# Sheet2.net
KiCad netlist of a schematic drawn in Altium Designer
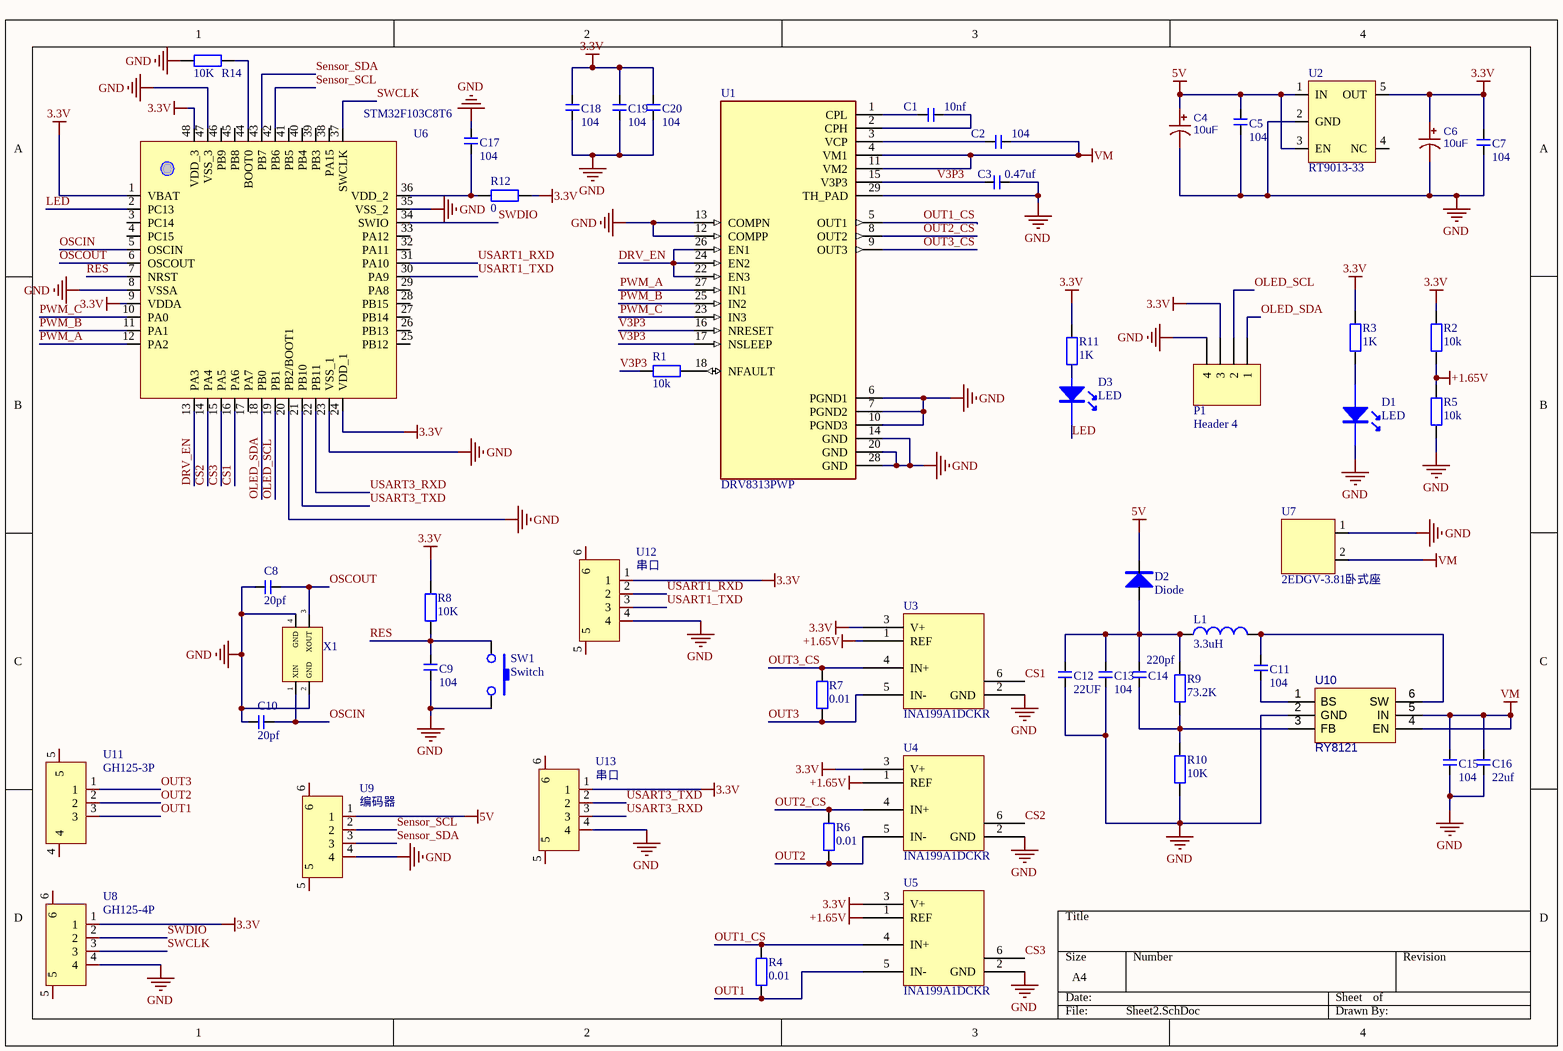
[diagram p0: Sheet2.SchDoc]

(export (version "E")
  (design (tool "Eeschema 10.0.6"))
  (components
    (comp (ref "C1")
      (value "10nf")
      (footprint "鹏鹏总结的pcb库:C0603")
      (description "无极性电容")
      (fields (field (name "版权归属") "源创客"))
      (libsource (lib "鹏鹏总结的原理库") (part "C"))
    )
    (comp (ref "C2")
      (value "104")
      (footprint "鹏鹏总结的pcb库:C0603")
      (description "无极性电容")
      (fields (field (name "版权归属") "源创客"))
      (libsource (lib "鹏鹏总结的原理库") (part "C"))
    )
    (comp (ref "C3")
      (value "0.47uf")
      (footprint "鹏鹏总结的pcb库:C0603")
      (description "无极性电容")
      (fields (field (name "版权归属") "源创客"))
      (libsource (lib "鹏鹏总结的原理库") (part "C"))
    )
    (comp (ref "C4")
      (value "10uF")
      (footprint "CD A(3216)")
      (description "电解电容 10uf  贴片型 钽电容的正极是实物有线的一段")
      (fields
        (field (name "BOM_MANUFACTURER PART") "RVT1V100M0405")
        (field (name "BOM_SUPPLIER PART") "C72485")
      )
      (libsource (lib "鹏鹏总结的原理库") (part "CAP+"))
    )
    (comp (ref "C5")
      (value "104")
      (footprint "鹏鹏总结的pcb库:C0603")
      (description "无极性电容")
      (fields (field (name "版权归属") "源创客"))
      (libsource (lib "鹏鹏总结的原理库") (part "C"))
    )
    (comp (ref "C6")
      (value "10uF")
      (footprint "CD A(3216)")
      (description "电解电容 10uf  贴片型 钽电容的正极是实物有线的一段")
      (fields
        (field (name "BOM_MANUFACTURER PART") "RVT1V100M0405")
        (field (name "BOM_SUPPLIER PART") "C72485")
      )
      (libsource (lib "鹏鹏总结的原理库") (part "CAP+"))
    )
    (comp (ref "C7")
      (value "104")
      (footprint "鹏鹏总结的pcb库:C0603")
      (description "无极性电容")
      (fields (field (name "版权归属") "源创客"))
      (libsource (lib "鹏鹏总结的原理库") (part "C"))
    )
    (comp (ref "C8")
      (value "20pf")
      (footprint "鹏鹏总结的pcb库:C0603")
      (description "无极性电容")
      (fields (field (name "版权归属") "源创客"))
      (libsource (lib "鹏鹏总结的原理库") (part "C"))
    )
    (comp (ref "C9")
      (value "104")
      (footprint "鹏鹏总结的pcb库:C0603")
      (description "无极性电容")
      (fields (field (name "版权归属") "源创客"))
      (libsource (lib "鹏鹏总结的原理库") (part "C"))
    )
    (comp (ref "C10")
      (value "20pf")
      (footprint "鹏鹏总结的pcb库:C0603")
      (description "无极性电容")
      (fields (field (name "版权归属") "源创客"))
      (libsource (lib "鹏鹏总结的原理库") (part "C"))
    )
    (comp (ref "C11")
      (value "104")
      (footprint "鹏鹏总结的pcb库:C0402")
      (description "无极性电容")
      (fields (field (name "版权归属") "源创客"))
      (libsource (lib "鹏鹏总结的原理库") (part "C"))
    )
    (comp (ref "C12")
      (value "22UF")
      (footprint "鹏鹏总结的pcb库:C0402")
      (description "无极性电容")
      (fields (field (name "版权归属") "源创客"))
      (libsource (lib "鹏鹏总结的原理库") (part "C"))
    )
    (comp (ref "C13")
      (value "104")
      (footprint "鹏鹏总结的pcb库:C0402")
      (description "无极性电容")
      (fields (field (name "版权归属") "源创客"))
      (libsource (lib "鹏鹏总结的原理库") (part "C"))
    )
    (comp (ref "C14")
      (value "220pf")
      (footprint "鹏鹏总结的pcb库:C0402")
      (description "无极性电容")
      (fields (field (name "版权归属") "源创客"))
      (libsource (lib "鹏鹏总结的原理库") (part "C"))
    )
    (comp (ref "C15")
      (value "104")
      (footprint "鹏鹏总结的pcb库:C0402")
      (description "无极性电容")
      (fields (field (name "版权归属") "源创客"))
      (libsource (lib "鹏鹏总结的原理库") (part "C"))
    )
    (comp (ref "C16")
      (value "22uf")
      (footprint "鹏鹏总结的pcb库:C0402")
      (description "无极性电容")
      (fields (field (name "版权归属") "源创客"))
      (libsource (lib "鹏鹏总结的原理库") (part "C"))
    )
    (comp (ref "C17")
      (value "104")
      (footprint "鹏鹏总结的pcb库:C0603")
      (description "无极性电容")
      (fields (field (name "版权归属") "源创客"))
      (libsource (lib "鹏鹏总结的原理库") (part "C"))
    )
    (comp (ref "C18")
      (value "104")
      (footprint "鹏鹏总结的pcb库:C0603")
      (description "无极性电容")
      (fields (field (name "版权归属") "源创客"))
      (libsource (lib "鹏鹏总结的原理库") (part "C"))
    )
    (comp (ref "C19")
      (value "104")
      (footprint "鹏鹏总结的pcb库:C0603")
      (description "无极性电容")
      (fields (field (name "版权归属") "源创客"))
      (libsource (lib "鹏鹏总结的原理库") (part "C"))
    )
    (comp (ref "C20")
      (value "104")
      (footprint "鹏鹏总结的pcb库:C0603")
      (description "无极性电容")
      (fields (field (name "版权归属") "源创客"))
      (libsource (lib "鹏鹏总结的原理库") (part "C"))
    )
    (comp (ref "D1") (value "LED") (footprint "LED0402") (libsource (lib "鹏鹏总结的原理库") (part "LED")))
    (comp (ref "D2")
      (value "Diode")
      (footprint "ESC_L1.2-W0.8-LS1.6-RD")
      (description "Diode 1N series")
      (libsource (lib "鹏鹏总结的原理库") (part "二极管"))
    )
    (comp (ref "D3") (value "LED") (footprint "LED0402") (libsource (lib "鹏鹏总结的原理库") (part "LED")))
    (comp (ref "L1")
      (value "3.3uH")
      (footprint "0402 TPC 4*4*2")
      (description "电感")
      (fields (field (name "版权归属") "源创客"))
      (libsource (lib "鹏鹏总结的原理库") (part "L"))
    )
    (comp (ref "P1")
      (value "Header 4")
      (footprint "HDR1X4")
      (description "Header, 4-Pin")
      (fields (field (name "PUBLISHER") "Altium Limited"))
      (libsource (lib "Miscellaneous Connectors") (part "Header 4"))
    )
    (comp (ref "R1")
      (value "10k")
      (footprint "鹏鹏总结的pcb库:R0603")
      (description "电阻")
      (fields (field (name "版权归属") "源创客"))
      (libsource (lib "鹏鹏总结的原理库") (part "R"))
    )
    (comp (ref "R2")
      (value "10k")
      (footprint "鹏鹏总结的pcb库:R0603")
      (description "电阻")
      (fields (field (name "版权归属") "源创客"))
      (libsource (lib "鹏鹏总结的原理库") (part "R"))
    )
    (comp (ref "R3")
      (value "1K")
      (footprint "R0402")
      (description "电阻")
      (fields (field (name "版权归属") "源创客"))
      (libsource (lib "鹏鹏总结的原理库") (part "R"))
    )
    (comp (ref "R4")
      (value "0.01")
      (footprint "R1206")
      (description "电阻")
      (fields (field (name "版权归属") "源创客"))
      (libsource (lib "鹏鹏总结的原理库") (part "R"))
    )
    (comp (ref "R5")
      (value "10k")
      (footprint "鹏鹏总结的pcb库:R0603")
      (description "电阻")
      (fields (field (name "版权归属") "源创客"))
      (libsource (lib "鹏鹏总结的原理库") (part "R"))
    )
    (comp (ref "R6")
      (value "0.01")
      (footprint "R1206")
      (description "电阻")
      (fields (field (name "版权归属") "源创客"))
      (libsource (lib "鹏鹏总结的原理库") (part "R"))
    )
    (comp (ref "R7")
      (value "0.01")
      (footprint "R1206")
      (description "电阻")
      (fields (field (name "版权归属") "源创客"))
      (libsource (lib "鹏鹏总结的原理库") (part "R"))
    )
    (comp (ref "R8")
      (value "10K")
      (footprint "鹏鹏总结的pcb库:R0603")
      (description "电阻")
      (fields (field (name "版权归属") "源创客"))
      (libsource (lib "鹏鹏总结的原理库") (part "R"))
    )
    (comp (ref "R9")
      (value "73.2K")
      (footprint "鹏鹏总结的pcb库:R0603")
      (description "电阻")
      (fields (field (name "版权归属") "源创客"))
      (libsource (lib "鹏鹏总结的原理库") (part "R"))
    )
    (comp (ref "R10")
      (value "10K")
      (footprint "鹏鹏总结的pcb库:R0603")
      (description "电阻")
      (fields (field (name "版权归属") "源创客"))
      (libsource (lib "鹏鹏总结的原理库") (part "R"))
    )
    (comp (ref "R11")
      (value "1K")
      (footprint "R0402")
      (description "电阻")
      (fields (field (name "版权归属") "源创客"))
      (libsource (lib "鹏鹏总结的原理库") (part "R"))
    )
    (comp (ref "R12")
      (value "0")
      (footprint "鹏鹏总结的pcb库:R0603")
      (description "电阻")
      (fields (field (name "版权归属") "源创客"))
      (libsource (lib "鹏鹏总结的原理库") (part "R"))
    )
    (comp (ref "R14")
      (value "10K")
      (footprint "鹏鹏总结的pcb库:R0603")
      (description "电阻")
      (fields (field (name "版权归属") "源创客"))
      (libsource (lib "鹏鹏总结的原理库") (part "R"))
    )
    (comp (ref "SW1")
      (value "Switch")
      (footprint "SW-SMD_L3.9-W3.6-LS4.8-EH")
      (description "SWITCH")
      (libsource (lib "鹏鹏总结的原理库") (part "Switch"))
    )
    (comp (ref "U1")
      (value "DRV8313PWP")
      (footprint "HTSSOP-28")
      (description "65-V max, 3-A peak 3-phase motor driver 28-HTSSOP -40 to 125")
      (fields (field (name "MF") "Texas Instruments"))
      (libsource (lib "鹏鹏总结的原理库") (part "DRV8313PWP"))
    )
    (comp (ref "U2")
      (value "RT9013-33")
      (footprint "SOT-23-5_L2.9-W1.6-P0.95-LS2.8-BR")
      (description "3.3V降压 500mA 最大输入5.5V")
      (libsource (lib "鹏鹏总结的原理库") (part "RT9013-33"))
    )
    (comp (ref "U3")
      (value "INA199A1DCKR")
      (footprint "SOT363")
      (libsource (lib "鹏鹏总结的原理库") (part "INA199A1DCKR"))
    )
    (comp (ref "U4")
      (value "INA199A1DCKR")
      (footprint "SOT363")
      (libsource (lib "鹏鹏总结的原理库") (part "INA199A1DCKR"))
    )
    (comp (ref "U5")
      (value "INA199A1DCKR")
      (footprint "SOT363")
      (libsource (lib "鹏鹏总结的原理库") (part "INA199A1DCKR"))
    )
    (comp (ref "U6")
      (value "STM32F103C8T6")
      (footprint "48P")
      (libsource (lib "鹏鹏总结的原理库") (part "STM32F103C8T6"))
    )
    (comp (ref "U7")
      (value "2EDGV-3.81卧式座")
      (footprint "2EDGV-3.81卧式座")
      (libsource (lib "鹏鹏总结的原理库") (part "2EDGV-3.81卧式座"))
    )
    (comp (ref "U8")
      (value "GH125-4P")
      (footprint "CONN-SMD_4P-P1.27_GH125-S04DCA-00")
      (libsource (lib "鹏鹏总结的原理库") (part "GH125-4P"))
    )
    (comp (ref "U9")
      (value "编码器")
      (footprint "CONN-SMD_4P-P1.27_GH125-S04DCA-00")
      (libsource (lib "鹏鹏总结的原理库") (part "GH125-4P"))
    )
    (comp (ref "U10")
      (value "RY8121")
      (footprint "SOT-23-6")
      (description "18V 2A 1MHz Synchronous Step-Down Regulator")
      (libsource (lib "鹏鹏总结的原理库") (part "RY8121"))
    )
    (comp (ref "U11")
      (value "GH125-3P")
      (footprint "CONN-SMD_3P-P1.27_JS_GH125-S03CCA-00")
      (libsource (lib "鹏鹏总结的原理库") (part "GH125-3P"))
    )
    (comp (ref "U12")
      (value "串口")
      (footprint "CONN-SMD_4P-P1.27_GH125-S04DCA-00")
      (libsource (lib "鹏鹏总结的原理库") (part "GH125-4P"))
    )
    (comp (ref "U13")
      (value "串口")
      (footprint "CONN-SMD_4P-P1.27_GH125-S04DCA-00")
      (libsource (lib "鹏鹏总结的原理库") (part "GH125-4P"))
    )
    (comp (ref "X1")
      (value "XTAL-4")
      (footprint "OSC-SMD_4P-L3.2-W2.5-BL")
      (description "贴片晶振")
      (libsource (lib "鹏鹏总结的原理库") (part "XTAL-4"))
    )
  )
  (nets
    (net (code "1") (name "+1.65V") (class "Default")
      (node (ref "R2") (pin "1") (pinfunction "1_1") (pintype "passive"))
      (node (ref "R5") (pin "2") (pinfunction "2_2") (pintype "passive"))
      (node (ref "U3") (pin "1") (pinfunction "REF_1") (pintype "passive"))
      (node (ref "U4") (pin "1") (pinfunction "REF_1") (pintype "passive"))
      (node (ref "U5") (pin "1") (pinfunction "REF_1") (pintype "passive"))
    )
    (net (code "2") (name "/CS1") (class "Default")
      (node (ref "U3") (pin "6") (pintype "passive"))
      (node (ref "U6") (pin "16") (pinfunction "PA6_16") (pintype "passive"))
    )
    (net (code "3") (name "/CS2") (class "Default")
      (node (ref "U4") (pin "6") (pintype "passive"))
      (node (ref "U6") (pin "14") (pinfunction "PA4_14") (pintype "passive"))
    )
    (net (code "4") (name "/CS3") (class "Default")
      (node (ref "U5") (pin "6") (pintype "passive"))
      (node (ref "U6") (pin "15") (pinfunction "PA5_15") (pintype "passive"))
    )
    (net (code "5") (name "/DRV_EN") (class "Default")
      (node (ref "U1") (pin "22") (pinfunction "EN3_22") (pintype "input"))
      (node (ref "U1") (pin "24") (pinfunction "EN2_24") (pintype "input"))
      (node (ref "U1") (pin "26") (pinfunction "EN1_26") (pintype "input"))
      (node (ref "U6") (pin "13") (pinfunction "PA3_13") (pintype "passive"))
    )
    (net (code "6") (name "/LED") (class "Default")
      (node (ref "D3") (pin "N") (pinfunction "2_N") (pintype "passive"))
      (node (ref "U6") (pin "2") (pinfunction "PC13_2") (pintype "passive"))
    )
    (net (code "7") (name "/OLED_SCL") (class "Default")
      (node (ref "P1") (pin "2") (pinfunction "2_2") (pintype "passive"))
      (node (ref "U6") (pin "19") (pinfunction "PB1_19") (pintype "passive"))
    )
    (net (code "8") (name "/OLED_SDA") (class "Default")
      (node (ref "P1") (pin "1") (pinfunction "1_1") (pintype "passive"))
      (node (ref "U6") (pin "18") (pinfunction "PB0_18") (pintype "passive"))
    )
    (net (code "9") (name "/OSCIN") (class "Default")
      (node (ref "C10") (pin "2") (pinfunction "2_2") (pintype "passive"))
      (node (ref "U6") (pin "5") (pinfunction "OSCIN_5") (pintype "passive"))
      (node (ref "X1") (pin "1") (pinfunction "XIN_1") (pintype "passive"))
    )
    (net (code "10") (name "/OSCOUT") (class "Default")
      (node (ref "C8") (pin "2") (pinfunction "2_2") (pintype "passive"))
      (node (ref "U6") (pin "6") (pinfunction "OSCOUT_6") (pintype "passive"))
      (node (ref "X1") (pin "3") (pinfunction "XOUT_3") (pintype "passive"))
    )
    (net (code "11") (name "/OUT1") (class "Default")
      (node (ref "R4") (pin "1") (pinfunction "1_1") (pintype "passive"))
      (node (ref "U11") (pin "3") (pinfunction "3_3") (pintype "passive"))
      (node (ref "U5") (pin "5") (pinfunction "IN-_5") (pintype "passive"))
    )
    (net (code "12") (name "/OUT1_CS") (class "Default")
      (node (ref "R4") (pin "2") (pinfunction "2_2") (pintype "passive"))
      (node (ref "U1") (pin "5") (pinfunction "OUT1_5") (pintype "output"))
      (node (ref "U5") (pin "4") (pinfunction "IN+_4") (pintype "passive"))
    )
    (net (code "13") (name "/OUT2") (class "Default")
      (node (ref "R6") (pin "1") (pinfunction "1_1") (pintype "passive"))
      (node (ref "U11") (pin "2") (pinfunction "2_2") (pintype "passive"))
      (node (ref "U4") (pin "5") (pinfunction "IN-_5") (pintype "passive"))
    )
    (net (code "14") (name "/OUT2_CS") (class "Default")
      (node (ref "R6") (pin "2") (pinfunction "2_2") (pintype "passive"))
      (node (ref "U1") (pin "8") (pinfunction "OUT2_8") (pintype "output"))
      (node (ref "U4") (pin "4") (pinfunction "IN+_4") (pintype "passive"))
    )
    (net (code "15") (name "/OUT3") (class "Default")
      (node (ref "R7") (pin "1") (pinfunction "1_1") (pintype "passive"))
      (node (ref "U11") (pin "1") (pinfunction "1_1") (pintype "passive"))
      (node (ref "U3") (pin "5") (pinfunction "IN-_5") (pintype "passive"))
    )
    (net (code "16") (name "/OUT3_CS") (class "Default")
      (node (ref "R7") (pin "2") (pinfunction "2_2") (pintype "passive"))
      (node (ref "U1") (pin "9") (pinfunction "OUT3_9") (pintype "output"))
      (node (ref "U3") (pin "4") (pinfunction "IN+_4") (pintype "passive"))
    )
    (net (code "17") (name "/PWM_A") (class "Default")
      (node (ref "U1") (pin "27") (pinfunction "IN1_27") (pintype "input"))
      (node (ref "U6") (pin "12") (pinfunction "PA2_12") (pintype "passive"))
    )
    (net (code "18") (name "/PWM_B") (class "Default")
      (node (ref "U1") (pin "25") (pinfunction "IN2_25") (pintype "input"))
      (node (ref "U6") (pin "11") (pinfunction "PA1_11") (pintype "passive"))
    )
    (net (code "19") (name "/PWM_C") (class "Default")
      (node (ref "U1") (pin "23") (pinfunction "IN3_23") (pintype "input"))
      (node (ref "U6") (pin "10") (pinfunction "PA0_10") (pintype "passive"))
    )
    (net (code "20") (name "/RES") (class "Default")
      (node (ref "C9") (pin "1") (pinfunction "1_1") (pintype "passive"))
      (node (ref "R8") (pin "1") (pinfunction "1_1") (pintype "passive"))
      (node (ref "SW1") (pin "1") (pinfunction "1_1") (pintype "passive"))
      (node (ref "U6") (pin "7") (pinfunction "NRST_7") (pintype "passive"))
    )
    (net (code "21") (name "/SWCLK") (class "Default")
      (node (ref "U6") (pin "37") (pinfunction "SWCLK_37") (pintype "passive"))
      (node (ref "U8") (pin "3") (pinfunction "3_3") (pintype "passive"))
    )
    (net (code "22") (name "/SWDIO") (class "Default")
      (node (ref "U6") (pin "34") (pinfunction "SWIO_34") (pintype "passive"))
      (node (ref "U8") (pin "2") (pinfunction "2_2") (pintype "passive"))
    )
    (net (code "23") (name "/Sensor_SCL") (class "Default")
      (node (ref "U6") (pin "42") (pinfunction "PB6_42") (pintype "passive"))
      (node (ref "U9") (pin "2") (pinfunction "2_2") (pintype "passive"))
    )
    (net (code "24") (name "/Sensor_SDA") (class "Default")
      (node (ref "U6") (pin "43") (pinfunction "PB7_43") (pintype "passive"))
      (node (ref "U9") (pin "3") (pinfunction "3_3") (pintype "passive"))
    )
    (net (code "25") (name "/USART1_RXD") (class "Default")
      (node (ref "U12") (pin "2") (pinfunction "2_2") (pintype "passive"))
      (node (ref "U6") (pin "31") (pinfunction "PA10_31") (pintype "passive"))
    )
    (net (code "26") (name "/USART1_TXD") (class "Default")
      (node (ref "U12") (pin "3") (pinfunction "3_3") (pintype "passive"))
      (node (ref "U6") (pin "30") (pinfunction "PA9_30") (pintype "passive"))
    )
    (net (code "27") (name "/USART3_RXD") (class "Default")
      (node (ref "U13") (pin "3") (pinfunction "3_3") (pintype "passive"))
      (node (ref "U6") (pin "22") (pinfunction "PB11_22") (pintype "passive"))
    )
    (net (code "28") (name "/USART3_TXD") (class "Default")
      (node (ref "U13") (pin "2") (pinfunction "2_2") (pintype "passive"))
      (node (ref "U6") (pin "21") (pinfunction "PB10_21") (pintype "passive"))
    )
    (net (code "29") (name "/V3P3") (class "Default")
      (node (ref "C3") (pin "1") (pinfunction "1_1") (pintype "passive"))
      (node (ref "R1") (pin "1") (pinfunction "1_1") (pintype "passive"))
      (node (ref "U1") (pin "15") (pinfunction "V3P3_15") (pintype "power_in"))
      (node (ref "U1") (pin "16") (pinfunction "NRESET_16") (pintype "input"))
      (node (ref "U1") (pin "17") (pinfunction "NSLEEP_17") (pintype "input"))
    )
    (net (code "30") (name "3.3V") (class "Default")
      (node (ref "C18") (pin "1") (pinfunction "1_1") (pintype "passive"))
      (node (ref "C19") (pin "1") (pinfunction "1_1") (pintype "passive"))
      (node (ref "C20") (pin "1") (pinfunction "1_1") (pintype "passive"))
      (node (ref "C6") (pin "1") (pintype "passive"))
      (node (ref "C7") (pin "2") (pinfunction "2_2") (pintype "passive"))
      (node (ref "P1") (pin "3") (pinfunction "3_3") (pintype "passive"))
      (node (ref "R11") (pin "1") (pinfunction "1_1") (pintype "passive"))
      (node (ref "R12") (pin "2") (pinfunction "2_2") (pintype "passive"))
      (node (ref "R2") (pin "2") (pinfunction "2_2") (pintype "passive"))
      (node (ref "R3") (pin "1") (pinfunction "1_1") (pintype "passive"))
      (node (ref "R8") (pin "2") (pinfunction "2_2") (pintype "passive"))
      (node (ref "U12") (pin "1") (pinfunction "1_1") (pintype "passive"))
      (node (ref "U13") (pin "1") (pinfunction "1_1") (pintype "passive"))
      (node (ref "U2") (pin "5") (pinfunction "OUT_5") (pintype "passive"))
      (node (ref "U3") (pin "3") (pinfunction "V+_3") (pintype "passive"))
      (node (ref "U4") (pin "3") (pinfunction "V+_3") (pintype "passive"))
      (node (ref "U5") (pin "3") (pinfunction "V+_3") (pintype "passive"))
      (node (ref "U6") (pin "1") (pinfunction "VBAT_1") (pintype "passive"))
      (node (ref "U6") (pin "24") (pinfunction "VDD_1_24") (pintype "passive"))
      (node (ref "U6") (pin "48") (pinfunction "VDD_3_48") (pintype "passive"))
      (node (ref "U6") (pin "9") (pinfunction "VDDA_9") (pintype "passive"))
      (node (ref "U8") (pin "1") (pinfunction "1_1") (pintype "passive"))
    )
    (net (code "31") (name "5V") (class "Default")
      (node (ref "C4") (pin "1") (pintype "passive"))
      (node (ref "C5") (pin "2") (pinfunction "2_2") (pintype "passive"))
      (node (ref "D2") (pin "1") (pintype "passive"))
      (node (ref "U2") (pin "1") (pinfunction "IN_1") (pintype "passive"))
      (node (ref "U2") (pin "3") (pinfunction "EN_3") (pintype "passive"))
      (node (ref "U9") (pin "1") (pinfunction "1_1") (pintype "passive"))
    )
    (net (code "32") (name "GND") (class "Default")
      (node (ref "C10") (pin "1") (pinfunction "1_1") (pintype "passive"))
      (node (ref "C12") (pin "1") (pinfunction "1_1") (pintype "passive"))
      (node (ref "C13") (pin "1") (pinfunction "1_1") (pintype "passive"))
      (node (ref "C15") (pin "1") (pinfunction "1_1") (pintype "passive"))
      (node (ref "C16") (pin "1") (pinfunction "1_1") (pintype "passive"))
      (node (ref "C17") (pin "1") (pinfunction "1_1") (pintype "passive"))
      (node (ref "C18") (pin "2") (pinfunction "2_2") (pintype "passive"))
      (node (ref "C19") (pin "2") (pinfunction "2_2") (pintype "passive"))
      (node (ref "C20") (pin "2") (pinfunction "2_2") (pintype "passive"))
      (node (ref "C3") (pin "2") (pinfunction "2_2") (pintype "passive"))
      (node (ref "C4") (pin "2") (pinfunction "2_2") (pintype "passive"))
      (node (ref "C5") (pin "1") (pinfunction "1_1") (pintype "passive"))
      (node (ref "C6") (pin "2") (pinfunction "2_2") (pintype "passive"))
      (node (ref "C7") (pin "1") (pinfunction "1_1") (pintype "passive"))
      (node (ref "C8") (pin "1") (pinfunction "1_1") (pintype "passive"))
      (node (ref "C9") (pin "2") (pinfunction "2_2") (pintype "passive"))
      (node (ref "D1") (pin "N") (pinfunction "2_N") (pintype "passive"))
      (node (ref "P1") (pin "4") (pinfunction "4_4") (pintype "passive"))
      (node (ref "R10") (pin "1") (pinfunction "1_1") (pintype "passive"))
      (node (ref "R14") (pin "1") (pinfunction "1_1") (pintype "passive"))
      (node (ref "R5") (pin "1") (pinfunction "1_1") (pintype "passive"))
      (node (ref "SW1") (pin "2") (pinfunction "2_2") (pintype "passive"))
      (node (ref "U1") (pin "10") (pinfunction "PGND3_10") (pintype "power_in"))
      (node (ref "U1") (pin "12") (pinfunction "COMPP_12") (pintype "input"))
      (node (ref "U1") (pin "13") (pinfunction "COMPN_13") (pintype "input"))
      (node (ref "U1") (pin "14") (pinfunction "GND_14") (pintype "power_in"))
      (node (ref "U1") (pin "20") (pinfunction "GND_20") (pintype "power_in"))
      (node (ref "U1") (pin "28") (pinfunction "GND_28") (pintype "power_in"))
      (node (ref "U1") (pin "29") (pinfunction "TH_PAD_29") (pintype "power_in"))
      (node (ref "U1") (pin "6") (pinfunction "PGND1_6") (pintype "power_in"))
      (node (ref "U1") (pin "7") (pinfunction "PGND2_7") (pintype "power_in"))
      (node (ref "U10") (pin "2") (pinfunction "GND_2") (pintype "passive"))
      (node (ref "U12") (pin "4") (pinfunction "4_4") (pintype "passive"))
      (node (ref "U13") (pin "4") (pinfunction "4_4") (pintype "passive"))
      (node (ref "U2") (pin "2") (pinfunction "GND_2") (pintype "passive"))
      (node (ref "U3") (pin "2") (pinfunction "GND_2") (pintype "passive"))
      (node (ref "U4") (pin "2") (pinfunction "GND_2") (pintype "passive"))
      (node (ref "U5") (pin "2") (pinfunction "GND_2") (pintype "passive"))
      (node (ref "U6") (pin "20") (pinfunction "PB2/BOOT1_20") (pintype "passive"))
      (node (ref "U6") (pin "23") (pinfunction "VSS_1_23") (pintype "passive"))
      (node (ref "U6") (pin "35") (pinfunction "VSS_2_35") (pintype "passive"))
      (node (ref "U6") (pin "47") (pinfunction "VSS_3_47") (pintype "passive"))
      (node (ref "U6") (pin "8") (pinfunction "VSSA_8") (pintype "passive"))
      (node (ref "U7") (pin "1") (pinfunction "1_1") (pintype "passive"))
      (node (ref "U8") (pin "4") (pinfunction "4_4") (pintype "passive"))
      (node (ref "U9") (pin "4") (pinfunction "4_4") (pintype "passive"))
      (node (ref "X1") (pin "2") (pinfunction "GND_2") (pintype "passive"))
      (node (ref "X1") (pin "4") (pinfunction "GND_4") (pintype "passive"))
    )
    (net (code "33") (name "Net-(C12-Pad2)") (class "Default")
      (node (ref "C12") (pin "2") (pinfunction "2_2") (pintype "passive"))
      (node (ref "C13") (pin "2") (pinfunction "2_2") (pintype "passive"))
      (node (ref "C14") (pin "2") (pinfunction "2_2") (pintype "passive"))
      (node (ref "D2") (pin "2") (pintype "passive"))
      (node (ref "L1") (pin "1") (pinfunction "1_1") (pintype "passive"))
      (node (ref "R9") (pin "2") (pinfunction "2_2") (pintype "passive"))
    )
    (net (code "34") (name "Net-(D1-1)") (class "Default")
      (node (ref "D1") (pin "A") (pinfunction "1_A") (pintype "passive"))
      (node (ref "R3") (pin "2") (pinfunction "2_2") (pintype "passive"))
    )
    (net (code "35") (name "Net-(D3-1)") (class "Default")
      (node (ref "D3") (pin "A") (pinfunction "1_A") (pintype "passive"))
      (node (ref "R11") (pin "2") (pinfunction "2_2") (pintype "passive"))
    )
    (net (code "36") (name "Net-(U1-CPH)") (class "Default")
      (node (ref "C1") (pin "1") (pinfunction "1_1") (pintype "passive"))
      (node (ref "U1") (pin "2") (pinfunction "CPH_2") (pintype "power_in"))
    )
    (net (code "37") (name "Net-(U1-CPL)") (class "Default")
      (node (ref "C1") (pin "2") (pinfunction "2_2") (pintype "passive"))
      (node (ref "U1") (pin "1") (pinfunction "CPL_1") (pintype "power_in"))
    )
    (net (code "38") (name "Net-(U1-NFAULT)") (class "Default")
      (node (ref "R1") (pin "2") (pinfunction "2_2") (pintype "passive"))
      (node (ref "U1") (pin "18") (pinfunction "NFAULT_18") (pintype "bidirectional"))
    )
    (net (code "39") (name "Net-(U1-VCP)") (class "Default")
      (node (ref "C2") (pin "2") (pinfunction "2_2") (pintype "passive"))
      (node (ref "U1") (pin "3") (pinfunction "VCP_3") (pintype "power_in"))
    )
    (net (code "40") (name "Net-(U6-BOOT0)") (class "Default")
      (node (ref "R14") (pin "2") (pinfunction "2_2") (pintype "passive"))
      (node (ref "U6") (pin "44") (pinfunction "BOOT0_44") (pintype "passive"))
    )
    (net (code "41") (name "Net-(U6-VDD_2)") (class "Default")
      (node (ref "C17") (pin "2") (pinfunction "2_2") (pintype "passive"))
      (node (ref "R12") (pin "1") (pinfunction "1_1") (pintype "passive"))
      (node (ref "U6") (pin "36") (pinfunction "VDD_2_36") (pintype "passive"))
    )
    (net (code "42") (name "Net-(U10-BS)") (class "Default")
      (node (ref "C11") (pin "1") (pinfunction "1_1") (pintype "passive"))
      (node (ref "U10") (pin "1") (pinfunction "BS_1") (pintype "passive"))
    )
    (net (code "43") (name "Net-(U10-FB)") (class "Default")
      (node (ref "C14") (pin "1") (pinfunction "1_1") (pintype "passive"))
      (node (ref "R10") (pin "2") (pinfunction "2_2") (pintype "passive"))
      (node (ref "R9") (pin "1") (pinfunction "1_1") (pintype "passive"))
      (node (ref "U10") (pin "3") (pinfunction "FB_3") (pintype "passive"))
    )
    (net (code "44") (name "Net-(U10-SW)") (class "Default")
      (node (ref "C11") (pin "2") (pinfunction "2_2") (pintype "passive"))
      (node (ref "L1") (pin "2") (pinfunction "2_2") (pintype "passive"))
      (node (ref "U10") (pin "6") (pinfunction "SW_6") (pintype "passive"))
    )
    (net (code "45") (name "VM") (class "Default")
      (node (ref "C15") (pin "2") (pinfunction "2_2") (pintype "passive"))
      (node (ref "C16") (pin "2") (pinfunction "2_2") (pintype "passive"))
      (node (ref "C2") (pin "1") (pinfunction "1_1") (pintype "passive"))
      (node (ref "U1") (pin "11") (pinfunction "VM2_11") (pintype "power_in"))
      (node (ref "U1") (pin "4") (pinfunction "VM1_4") (pintype "power_in"))
      (node (ref "U10") (pin "4") (pinfunction "EN_4") (pintype "passive"))
      (node (ref "U10") (pin "5") (pinfunction "IN_5") (pintype "passive"))
      (node (ref "U7") (pin "2") (pinfunction "2_2") (pintype "passive"))
    )
    (net (code "46") (name "unconnected-(U2-NC-Pad4)") (class "Default")
      (node (ref "U2") (pin "4") (pinfunction "NC_4") (pintype "passive"))
    )
    (net (code "47") (name "unconnected-(U6-PA7-Pad17)") (class "Default")
      (node (ref "U6") (pin "17") (pinfunction "PA7_17") (pintype "passive"))
    )
    (net (code "48") (name "unconnected-(U6-PA8-Pad29)") (class "Default")
      (node (ref "U6") (pin "29") (pinfunction "PA8_29") (pintype "passive"))
    )
    (net (code "49") (name "unconnected-(U6-PA11-Pad32)") (class "Default")
      (node (ref "U6") (pin "32") (pinfunction "PA11_32") (pintype "passive"))
    )
    (net (code "50") (name "unconnected-(U6-PA12-Pad33)") (class "Default")
      (node (ref "U6") (pin "33") (pinfunction "PA12_33") (pintype "passive"))
    )
    (net (code "51") (name "unconnected-(U6-PA15-Pad38)") (class "Default")
      (node (ref "U6") (pin "38") (pinfunction "PA15_38") (pintype "passive"))
    )
    (net (code "52") (name "unconnected-(U6-PB3-Pad39)") (class "Default")
      (node (ref "U6") (pin "39") (pinfunction "PB3_39") (pintype "passive"))
    )
    (net (code "53") (name "unconnected-(U6-PB4-Pad40)") (class "Default")
      (node (ref "U6") (pin "40") (pinfunction "PB4_40") (pintype "passive"))
    )
    (net (code "54") (name "unconnected-(U6-PB5-Pad41)") (class "Default")
      (node (ref "U6") (pin "41") (pinfunction "PB5_41") (pintype "passive"))
    )
    (net (code "55") (name "unconnected-(U6-PB8-Pad45)") (class "Default")
      (node (ref "U6") (pin "45") (pinfunction "PB8_45") (pintype "passive"))
    )
    (net (code "56") (name "unconnected-(U6-PB9-Pad46)") (class "Default")
      (node (ref "U6") (pin "46") (pinfunction "PB9_46") (pintype "passive"))
    )
    (net (code "57") (name "unconnected-(U6-PB12-Pad25)") (class "Default")
      (node (ref "U6") (pin "25") (pinfunction "PB12_25") (pintype "passive"))
    )
    (net (code "58") (name "unconnected-(U6-PB13-Pad26)") (class "Default")
      (node (ref "U6") (pin "26") (pinfunction "PB13_26") (pintype "passive"))
    )
    (net (code "59") (name "unconnected-(U6-PB14-Pad27)") (class "Default")
      (node (ref "U6") (pin "27") (pinfunction "PB14_27") (pintype "passive"))
    )
    (net (code "60") (name "unconnected-(U6-PB15-Pad28)") (class "Default")
      (node (ref "U6") (pin "28") (pinfunction "PB15_28") (pintype "passive"))
    )
    (net (code "61") (name "unconnected-(U6-PC14-Pad3)") (class "Default")
      (node (ref "U6") (pin "3") (pinfunction "PC14_3") (pintype "passive"))
    )
    (net (code "62") (name "unconnected-(U6-PC15-Pad4)") (class "Default")
      (node (ref "U6") (pin "4") (pinfunction "PC15_4") (pintype "passive"))
    )
    (net (code "63") (name "unconnected-(U8-Pad5)") (class "Default")
      (node (ref "U8") (pin "5") (pinfunction "5_5") (pintype "passive"))
    )
    (net (code "64") (name "unconnected-(U8-Pad6)") (class "Default")
      (node (ref "U8") (pin "6") (pinfunction "6_6") (pintype "passive"))
    )
    (net (code "65") (name "unconnected-(U9-Pad5)") (class "Default")
      (node (ref "U9") (pin "5") (pinfunction "5_5") (pintype "passive"))
    )
    (net (code "66") (name "unconnected-(U9-Pad6)") (class "Default")
      (node (ref "U9") (pin "6") (pinfunction "6_6") (pintype "passive"))
    )
    (net (code "67") (name "unconnected-(U11-Pad4)") (class "Default")
      (node (ref "U11") (pin "4") (pinfunction "4_4") (pintype "passive"))
    )
    (net (code "68") (name "unconnected-(U11-Pad5)") (class "Default")
      (node (ref "U11") (pin "5") (pinfunction "5_5") (pintype "passive"))
    )
    (net (code "69") (name "unconnected-(U12-Pad5)") (class "Default")
      (node (ref "U12") (pin "5") (pinfunction "5_5") (pintype "passive"))
    )
    (net (code "70") (name "unconnected-(U12-Pad6)") (class "Default")
      (node (ref "U12") (pin "6") (pinfunction "6_6") (pintype "passive"))
    )
    (net (code "71") (name "unconnected-(U13-Pad5)") (class "Default")
      (node (ref "U13") (pin "5") (pinfunction "5_5") (pintype "passive"))
    )
    (net (code "72") (name "unconnected-(U13-Pad6)") (class "Default")
      (node (ref "U13") (pin "6") (pinfunction "6_6") (pintype "passive"))
    )
  )
)
